# ProPrj_Arduino_Project_2026-04-11_1.net
KiCad netlist of a schematic drawn in EasyEDA Pro
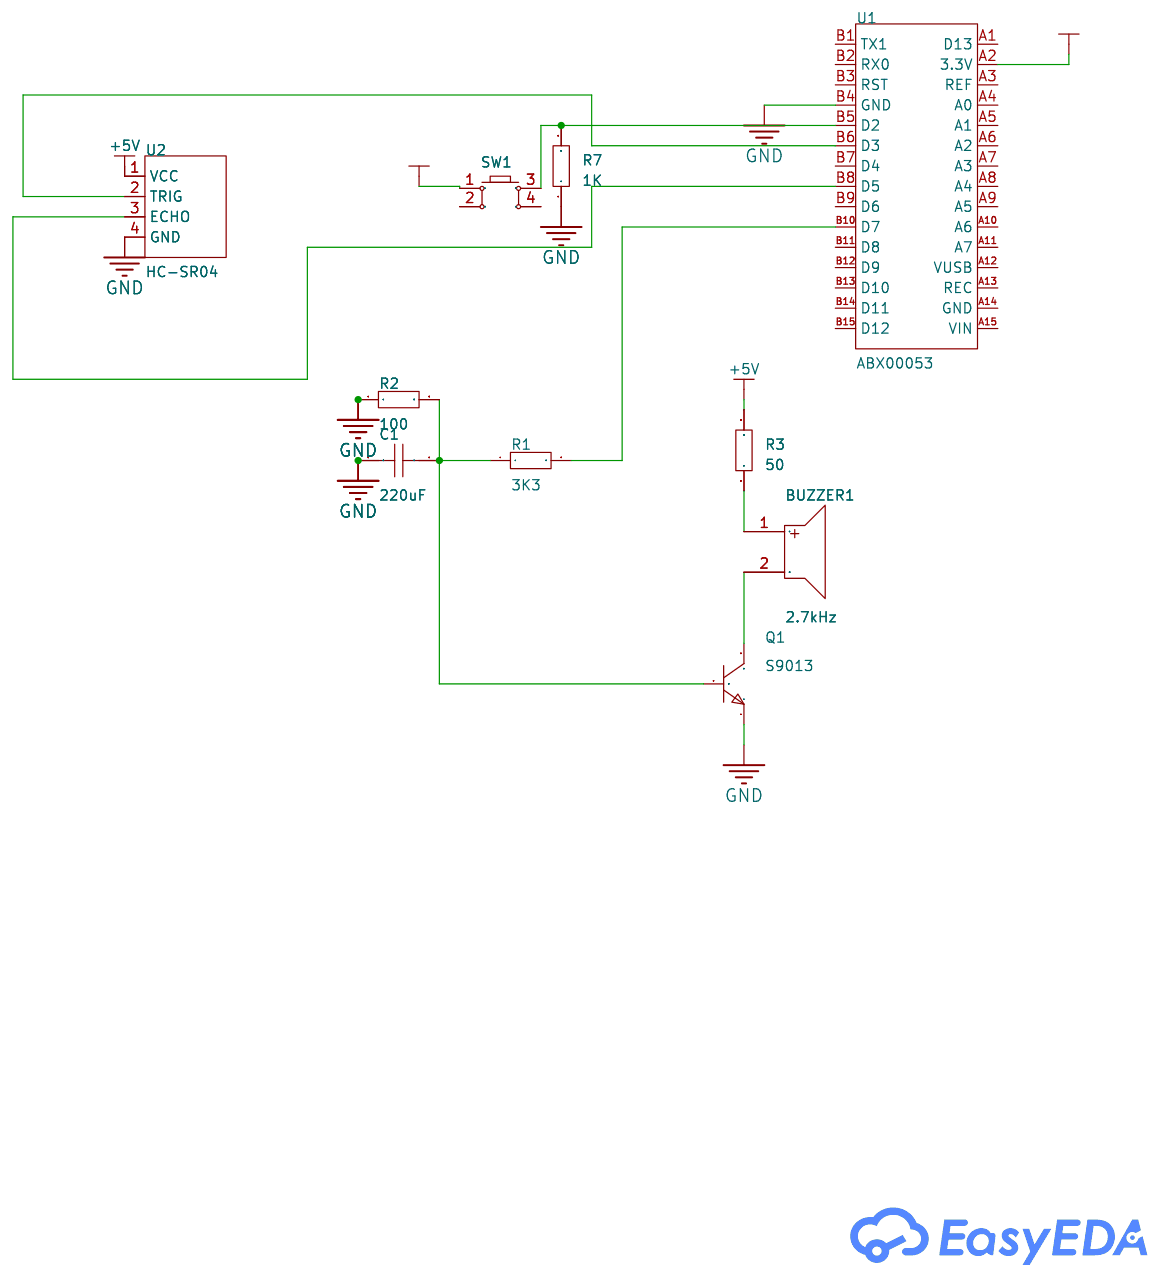
[diagram p0: schematic sheet]

(export (version "E")
  (design (tool "Eeschema 10.0.6"))
  (components
    (comp (ref "BUZZER1")
      (value "2.7kHz")
      (footprint "easyedapro:BUZ-TH_BD9.0-P4.00-D0.6-FD")
      (fields (field (name "Manufacturer Part") "QMB-09B-03") (field (name "Manufacturer") "华能"))
      (libsource (lib "easyedapro") (part "QMB-09B-03"))
    )
    (comp (ref "C1")
      (value "220uF")
      (footprint "easyedapro:C0201")
      (libsource (lib "easyedapro") (part "CAP"))
    )
    (comp (ref "Q1")
      (value "S9013")
      (footprint "easyedapro:TO-92-3_L4.5-W3.5-P1.27-L")
      (fields (field (name "Manufacturer") "HXY MOSFET(华轩阳电子)"))
      (libsource (lib "easyedapro") (part "S9013_C20616377"))
    )
    (comp (ref "R1") (value "3K3") (footprint "easyedapro:R0603") (libsource (lib "easyedapro") (part "Res")))
    (comp (ref "R2") (value "100") (footprint "easyedapro:R0603") (libsource (lib "easyedapro") (part "Res")))
    (comp (ref "R3") (value "50") (footprint "easyedapro:R0603") (libsource (lib "easyedapro") (part "Res")))
    (comp (ref "R7") (value "1K") (footprint "easyedapro:R0603") (libsource (lib "easyedapro") (part "Res")))
    (comp (ref "SW1")
      (value "~")
      (footprint "easyedapro:SW-SMD_4P-L6.0-W6.0-P4.50-LS9.0-2")
      (libsource (lib "easyedapro") (part "轻触按键"))
    )
    (comp (ref "U1")
      (value "ABX00053")
      (footprint "easyedapro:COMM-TH_ABX00092")
      (fields (field (name "Manufacturer") "arduino"))
      (libsource (lib "easyedapro") (part "ABX00053"))
    )
    (comp (ref "U2")
      (value "HC-SR04")
      (footprint "easyedapro:TH_HC-SR04V")
      (fields (field (name "Manufacturer") "Universal Microelectronics"))
      (libsource (lib "easyedapro") (part "HC-SR04"))
    )
  )
  (nets
    (net (code "1") (name "+5V") (class "Default")
      (node (ref "R3") (pin "2") (pinfunction "2_2") (pintype "input"))
      (node (ref "U2") (pin "1") (pinfunction "VCC_1") (pintype "unspecified"))
    )
    (net (code "2") (name "3.3V") (class "Default")
      (node (ref "U1") (pin "A2") (pinfunction "3.3V_A2") (pintype "unspecified"))
    )
    (net (code "3") (name "5V") (class "Default")
      (node (ref "SW1") (pin "1") (pinfunction "1_1") (pintype "input"))
    )
    (net (code "4") (name "GND") (class "Default")
      (node (ref "C1") (pin "2") (pinfunction "2_2") (pintype "input"))
      (node (ref "Q1") (pin "1") (pinfunction "E_1") (pintype "unspecified"))
      (node (ref "R2") (pin "1") (pinfunction "1_1") (pintype "input"))
      (node (ref "R7") (pin "1") (pinfunction "1_1") (pintype "input"))
      (node (ref "U1") (pin "B4") (pinfunction "GND_B4") (pintype "unspecified"))
      (node (ref "U2") (pin "4") (pinfunction "GND_4") (pintype "unspecified"))
    )
    (net (code "5") (name "Net-(BUZZER1-Pad1)") (class "Default")
      (node (ref "BUZZER1") (pin "1") (pinfunction "1_1") (pintype "unspecified"))
      (node (ref "R3") (pin "1") (pinfunction "1_1") (pintype "input"))
    )
    (net (code "6") (name "Net-(Q1-B)") (class "Default")
      (node (ref "C1") (pin "1") (pinfunction "1_1") (pintype "input"))
      (node (ref "Q1") (pin "2") (pinfunction "B_2") (pintype "unspecified"))
      (node (ref "R1") (pin "1") (pinfunction "1_1") (pintype "input"))
      (node (ref "R2") (pin "2") (pinfunction "2_2") (pintype "input"))
    )
    (net (code "7") (name "Net-(Q1-C)") (class "Default")
      (node (ref "BUZZER1") (pin "2") (pinfunction "2_2") (pintype "unspecified"))
      (node (ref "Q1") (pin "3") (pinfunction "C_3") (pintype "unspecified"))
    )
    (net (code "8") (name "Net-(U1-D2)") (class "Default")
      (node (ref "R7") (pin "2") (pinfunction "2_2") (pintype "input"))
      (node (ref "SW1") (pin "3") (pinfunction "3_3") (pintype "input"))
      (node (ref "U1") (pin "B5") (pinfunction "D2_B5") (pintype "unspecified"))
    )
    (net (code "9") (name "Net-(U1-D3)") (class "Default")
      (node (ref "U1") (pin "B6") (pinfunction "D3_B6") (pintype "unspecified"))
      (node (ref "U2") (pin "2") (pinfunction "TRIG_2") (pintype "unspecified"))
    )
    (net (code "10") (name "Net-(U1-D5)") (class "Default")
      (node (ref "U1") (pin "B8") (pinfunction "D5_B8") (pintype "unspecified"))
      (node (ref "U2") (pin "3") (pinfunction "ECHO_3") (pintype "unspecified"))
    )
    (net (code "11") (name "Net-(U1-D7)") (class "Default")
      (node (ref "R1") (pin "2") (pinfunction "2_2") (pintype "input"))
      (node (ref "U1") (pin "B10") (pinfunction "D7_B10") (pintype "unspecified"))
    )
    (net (code "12") (name "unconnected-(SW1-Pad2)") (class "Default")
      (node (ref "SW1") (pin "2") (pinfunction "2_2") (pintype "input"))
    )
    (net (code "13") (name "unconnected-(SW1-Pad4)") (class "Default")
      (node (ref "SW1") (pin "4") (pinfunction "4_4") (pintype "input"))
    )
    (net (code "14") (name "unconnected-(U1-A0-PadA4)") (class "Default")
      (node (ref "U1") (pin "A4") (pinfunction "A0_A4") (pintype "unspecified"))
    )
    (net (code "15") (name "unconnected-(U1-A1-PadA5)") (class "Default")
      (node (ref "U1") (pin "A5") (pinfunction "A1_A5") (pintype "unspecified"))
    )
    (net (code "16") (name "unconnected-(U1-A2-PadA6)") (class "Default")
      (node (ref "U1") (pin "A6") (pinfunction "A2_A6") (pintype "unspecified"))
    )
    (net (code "17") (name "unconnected-(U1-A3-PadA7)") (class "Default")
      (node (ref "U1") (pin "A7") (pinfunction "A3_A7") (pintype "unspecified"))
    )
    (net (code "18") (name "unconnected-(U1-A4-PadA8)") (class "Default")
      (node (ref "U1") (pin "A8") (pinfunction "A4_A8") (pintype "unspecified"))
    )
    (net (code "19") (name "unconnected-(U1-A5-PadA9)") (class "Default")
      (node (ref "U1") (pin "A9") (pinfunction "A5_A9") (pintype "unspecified"))
    )
    (net (code "20") (name "unconnected-(U1-A6-PadA10)") (class "Default")
      (node (ref "U1") (pin "A10") (pinfunction "A6_A10") (pintype "unspecified"))
    )
    (net (code "21") (name "unconnected-(U1-A7-PadA11)") (class "Default")
      (node (ref "U1") (pin "A11") (pinfunction "A7_A11") (pintype "unspecified"))
    )
    (net (code "22") (name "unconnected-(U1-D4-PadB7)") (class "Default")
      (node (ref "U1") (pin "B7") (pinfunction "D4_B7") (pintype "unspecified"))
    )
    (net (code "23") (name "unconnected-(U1-D6-PadB9)") (class "Default")
      (node (ref "U1") (pin "B9") (pinfunction "D6_B9") (pintype "unspecified"))
    )
    (net (code "24") (name "unconnected-(U1-D8-PadB11)") (class "Default")
      (node (ref "U1") (pin "B11") (pinfunction "D8_B11") (pintype "unspecified"))
    )
    (net (code "25") (name "unconnected-(U1-D9-PadB12)") (class "Default")
      (node (ref "U1") (pin "B12") (pinfunction "D9_B12") (pintype "unspecified"))
    )
    (net (code "26") (name "unconnected-(U1-D10-PadB13)") (class "Default")
      (node (ref "U1") (pin "B13") (pinfunction "D10_B13") (pintype "unspecified"))
    )
    (net (code "27") (name "unconnected-(U1-D11-PadB14)") (class "Default")
      (node (ref "U1") (pin "B14") (pinfunction "D11_B14") (pintype "unspecified"))
    )
    (net (code "28") (name "unconnected-(U1-D12-PadB15)") (class "Default")
      (node (ref "U1") (pin "B15") (pinfunction "D12_B15") (pintype "unspecified"))
    )
    (net (code "29") (name "unconnected-(U1-D13-PadA1)") (class "Default")
      (node (ref "U1") (pin "A1") (pinfunction "D13_A1") (pintype "unspecified"))
    )
    (net (code "30") (name "unconnected-(U1-GND-PadA14)") (class "Default")
      (node (ref "U1") (pin "A14") (pinfunction "GND_A14") (pintype "unspecified"))
    )
    (net (code "31") (name "unconnected-(U1-REC-PadA13)") (class "Default")
      (node (ref "U1") (pin "A13") (pinfunction "REC_A13") (pintype "unspecified"))
    )
    (net (code "32") (name "unconnected-(U1-REF-PadA3)") (class "Default")
      (node (ref "U1") (pin "A3") (pinfunction "REF_A3") (pintype "unspecified"))
    )
    (net (code "33") (name "unconnected-(U1-RST-PadB3)") (class "Default")
      (node (ref "U1") (pin "B3") (pinfunction "RST_B3") (pintype "unspecified"))
    )
    (net (code "34") (name "unconnected-(U1-RX0-PadB2)") (class "Default")
      (node (ref "U1") (pin "B2") (pinfunction "RX0_B2") (pintype "unspecified"))
    )
    (net (code "35") (name "unconnected-(U1-TX1-PadB1)") (class "Default")
      (node (ref "U1") (pin "B1") (pinfunction "TX1_B1") (pintype "unspecified"))
    )
    (net (code "36") (name "unconnected-(U1-VIN-PadA15)") (class "Default")
      (node (ref "U1") (pin "A15") (pinfunction "VIN_A15") (pintype "unspecified"))
    )
    (net (code "37") (name "unconnected-(U1-VUSB-PadA12)") (class "Default")
      (node (ref "U1") (pin "A12") (pinfunction "VUSB_A12") (pintype "unspecified"))
    )
  )
)
